# DAC_12bitController.net
KiCad netlist of a schematic drawn in EAGLE
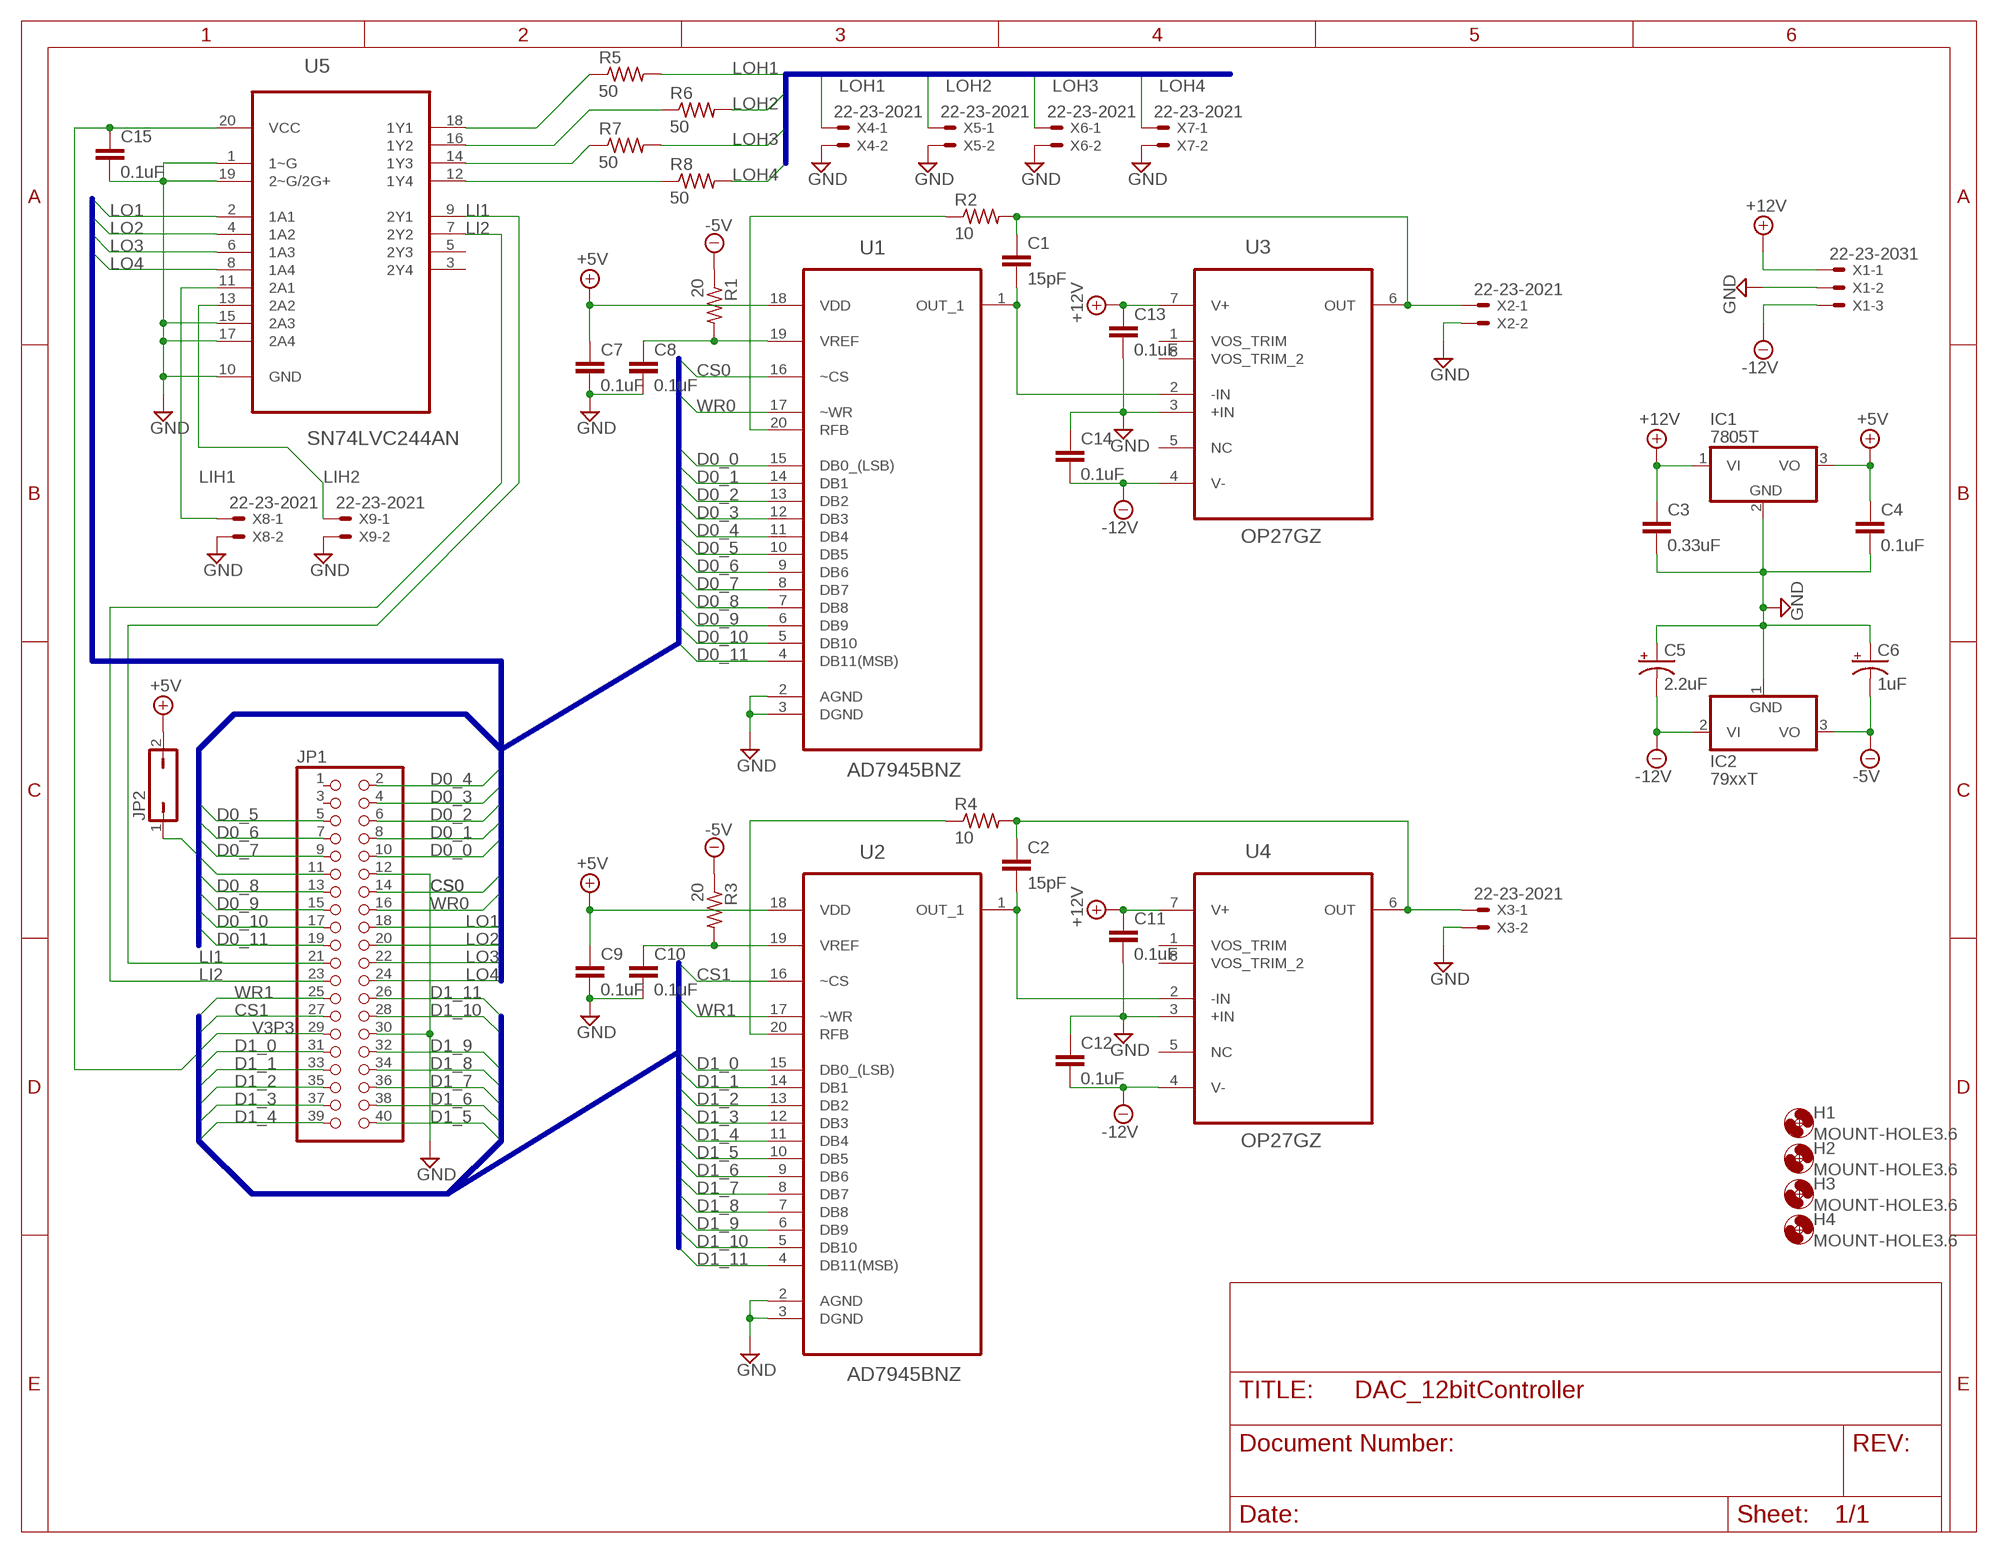
[diagram p0: schematic, sheet 1]

(export (version "E")
  (design (tool "Eeschema 10.0.6"))
  (components
    (comp (ref "C1")
      (value "15pF")
      (footprint "eagle-import:C5B2.5")
      (libsource (lib "eagle-import") (part "C5/2.5"))
    )
    (comp (ref "C2")
      (value "15pF")
      (footprint "eagle-import:C5B2.5")
      (libsource (lib "eagle-import") (part "C5/2.5"))
    )
    (comp (ref "C3")
      (value "0.33uF")
      (footprint "eagle-import:C5B2.5")
      (libsource (lib "eagle-import") (part "C5/2.5"))
    )
    (comp (ref "C4")
      (value "0.1uF")
      (footprint "eagle-import:C5B2.5")
      (libsource (lib "eagle-import") (part "C5/2.5"))
    )
    (comp (ref "C5")
      (value "2.2uF")
      (footprint "eagle-import:E2,5-7")
      (libsource (lib "eagle-import") (part "CPOL-USE2.5-7"))
    )
    (comp (ref "C6")
      (value "1uF")
      (footprint "eagle-import:E2,5-7")
      (libsource (lib "eagle-import") (part "CPOL-USE2.5-7"))
    )
    (comp (ref "C7")
      (value "0.1uF")
      (footprint "eagle-import:C5B2.5")
      (libsource (lib "eagle-import") (part "C5/2.5"))
    )
    (comp (ref "C8")
      (value "0.1uF")
      (footprint "eagle-import:C5B2.5")
      (libsource (lib "eagle-import") (part "C5/2.5"))
    )
    (comp (ref "C9")
      (value "0.1uF")
      (footprint "eagle-import:C5B2.5")
      (libsource (lib "eagle-import") (part "C5/2.5"))
    )
    (comp (ref "C10")
      (value "0.1uF")
      (footprint "eagle-import:C5B2.5")
      (libsource (lib "eagle-import") (part "C5/2.5"))
    )
    (comp (ref "C11")
      (value "0.1uF")
      (footprint "eagle-import:C5B2.5")
      (libsource (lib "eagle-import") (part "C5/2.5"))
    )
    (comp (ref "C12")
      (value "0.1uF")
      (footprint "eagle-import:C5B2.5")
      (libsource (lib "eagle-import") (part "C5/2.5"))
    )
    (comp (ref "C13")
      (value "0.1uF")
      (footprint "eagle-import:C5B2.5")
      (libsource (lib "eagle-import") (part "C5/2.5"))
    )
    (comp (ref "C14")
      (value "0.1uF")
      (footprint "eagle-import:C5B2.5")
      (libsource (lib "eagle-import") (part "C5/2.5"))
    )
    (comp (ref "C15")
      (value "0.1uF")
      (footprint "eagle-import:C5B2.5")
      (libsource (lib "eagle-import") (part "C5/2.5"))
    )
    (comp (ref "H1")
      (value "MOUNT-HOLE3.6")
      (footprint "eagle-import:3,6")
      (libsource (lib "eagle-import") (part "MOUNT-HOLE3.6"))
    )
    (comp (ref "H2")
      (value "MOUNT-HOLE3.6")
      (footprint "eagle-import:3,6")
      (libsource (lib "eagle-import") (part "MOUNT-HOLE3.6"))
    )
    (comp (ref "H3")
      (value "MOUNT-HOLE3.6")
      (footprint "eagle-import:3,6")
      (libsource (lib "eagle-import") (part "MOUNT-HOLE3.6"))
    )
    (comp (ref "H4")
      (value "MOUNT-HOLE3.6")
      (footprint "eagle-import:3,6")
      (libsource (lib "eagle-import") (part "MOUNT-HOLE3.6"))
    )
    (comp (ref "IC1")
      (value "7805T")
      (footprint "eagle-import:TO220H")
      (libsource (lib "eagle-import") (part "78T05"))
    )
    (comp (ref "IC2")
      (value "79xxT")
      (footprint "eagle-import:TO220H")
      (libsource (lib "eagle-import") (part "79T05"))
    )
    (comp (ref "JP1")
      (value "PINHD-2X20")
      (footprint "eagle-import:2X20")
      (libsource (lib "eagle-import") (part "PINHD-2X20"))
    )
    (comp (ref "JP2")
      (value "JP1Q")
      (footprint "eagle-import:JP1")
      (libsource (lib "eagle-import") (part "JP1Q"))
    )
    (comp (ref "R1")
      (value "20")
      (footprint "eagle-import:0207_10")
      (libsource (lib "eagle-import") (part "R-US_0207/10"))
    )
    (comp (ref "R2")
      (value "10")
      (footprint "eagle-import:0207_10")
      (libsource (lib "eagle-import") (part "R-US_0207/10"))
    )
    (comp (ref "R3")
      (value "20")
      (footprint "eagle-import:0207_10")
      (libsource (lib "eagle-import") (part "R-US_0207/10"))
    )
    (comp (ref "R4")
      (value "10")
      (footprint "eagle-import:0207_10")
      (libsource (lib "eagle-import") (part "R-US_0207/10"))
    )
    (comp (ref "R5")
      (value "50")
      (footprint "eagle-import:0207_10")
      (libsource (lib "eagle-import") (part "R-US_0207/10"))
    )
    (comp (ref "R6")
      (value "50")
      (footprint "eagle-import:0207_10")
      (libsource (lib "eagle-import") (part "R-US_0207/10"))
    )
    (comp (ref "R7")
      (value "50")
      (footprint "eagle-import:0207_10")
      (libsource (lib "eagle-import") (part "R-US_0207/10"))
    )
    (comp (ref "R8")
      (value "50")
      (footprint "eagle-import:0207_10")
      (libsource (lib "eagle-import") (part "R-US_0207/10"))
    )
    (comp (ref "U1")
      (value "AD7945BNZ")
      (footprint "eagle-import:DIP254P762X368-20")
      (fields (field (name "MPN") "AD7545AKNZ"))
      (libsource (lib "eagle-import") (part "AD7545AKNZ"))
    )
    (comp (ref "U2")
      (value "AD7945BNZ")
      (footprint "eagle-import:DIP254P762X368-20")
      (fields (field (name "MPN") "AD7545AKNZ"))
      (libsource (lib "eagle-import") (part "AD7545AKNZ"))
    )
    (comp (ref "U3")
      (value "OP27GZ")
      (footprint "eagle-import:DIP254P762X508-8")
      (libsource (lib "eagle-import") (part "OP27GZ"))
    )
    (comp (ref "U4")
      (value "OP27GZ")
      (footprint "eagle-import:DIP254P762X508-8")
      (libsource (lib "eagle-import") (part "OP27GZ"))
    )
    (comp (ref "U5")
      (value "SN74LVC244AN")
      (footprint "eagle-import:DIP254P762X508-20")
      (fields (field (name "MPN") "SN74LS244N"))
      (libsource (lib "eagle-import") (part "SN74LS244N"))
    )
    (comp (ref "X1")
      (value "22-23-2031")
      (footprint "eagle-import:22-23-2031")
      (fields (field (name "MF") "MOLEX"))
      (libsource (lib "eagle-import") (part "22-23-2031"))
    )
    (comp (ref "X2")
      (value "22-23-2021")
      (footprint "eagle-import:22-23-2021")
      (fields (field (name "MF") "MOLEX"))
      (libsource (lib "eagle-import") (part "22-23-2021"))
    )
    (comp (ref "X3")
      (value "22-23-2021")
      (footprint "eagle-import:22-23-2021")
      (fields (field (name "MF") "MOLEX"))
      (libsource (lib "eagle-import") (part "22-23-2021"))
    )
    (comp (ref "X4")
      (value "22-23-2021")
      (footprint "eagle-import:22-23-2021")
      (fields (field (name "MF") "MOLEX"))
      (libsource (lib "eagle-import") (part "22-23-2021"))
    )
    (comp (ref "X5")
      (value "22-23-2021")
      (footprint "eagle-import:22-23-2021")
      (fields (field (name "MF") "MOLEX"))
      (libsource (lib "eagle-import") (part "22-23-2021"))
    )
    (comp (ref "X6")
      (value "22-23-2021")
      (footprint "eagle-import:22-23-2021")
      (fields (field (name "MF") "MOLEX"))
      (libsource (lib "eagle-import") (part "22-23-2021"))
    )
    (comp (ref "X7")
      (value "22-23-2021")
      (footprint "eagle-import:22-23-2021")
      (fields (field (name "MF") "MOLEX"))
      (libsource (lib "eagle-import") (part "22-23-2021"))
    )
    (comp (ref "X8")
      (value "22-23-2021")
      (footprint "eagle-import:22-23-2021")
      (fields (field (name "MF") "MOLEX"))
      (libsource (lib "eagle-import") (part "22-23-2021"))
    )
    (comp (ref "X9")
      (value "22-23-2021")
      (footprint "eagle-import:22-23-2021")
      (fields (field (name "MF") "MOLEX"))
      (libsource (lib "eagle-import") (part "22-23-2021"))
    )
  )
  (nets
    (net (code "1") (name "+5V") (class "Default")
      (node (ref "C4") (pin "1") (pinfunction "1_1") (pintype "passive"))
      (node (ref "C7") (pin "1") (pinfunction "1_1") (pintype "passive"))
      (node (ref "C9") (pin "1") (pinfunction "1_1") (pintype "passive"))
      (node (ref "IC1") (pin "3") (pinfunction "VO_3") (pintype "passive"))
      (node (ref "JP2") (pin "2") (pinfunction "2_2") (pintype "passive"))
      (node (ref "U1") (pin "18") (pinfunction "VDD_18") (pintype "power_in"))
      (node (ref "U2") (pin "18") (pinfunction "VDD_18") (pintype "power_in"))
    )
    (net (code "2") (name "+12V") (class "Default")
      (node (ref "C11") (pin "1") (pinfunction "1_1") (pintype "passive"))
      (node (ref "C13") (pin "1") (pinfunction "1_1") (pintype "passive"))
      (node (ref "C3") (pin "1") (pinfunction "1_1") (pintype "passive"))
      (node (ref "IC1") (pin "1") (pinfunction "VI_1") (pintype "input"))
      (node (ref "U3") (pin "7") (pinfunction "V+_7") (pintype "power_in"))
      (node (ref "U4") (pin "7") (pinfunction "V+_7") (pintype "power_in"))
      (node (ref "X1") (pin "1") (pinfunction "S_1") (pintype "passive"))
    )
    (net (code "3") (name "-5V") (class "Default")
      (node (ref "C6") (pin "-") (pinfunction "-_-") (pintype "passive"))
      (node (ref "IC2") (pin "3") (pinfunction "VO_3") (pintype "passive"))
      (node (ref "R1") (pin "1") (pinfunction "1_1") (pintype "passive"))
      (node (ref "R3") (pin "1") (pinfunction "1_1") (pintype "passive"))
    )
    (net (code "4") (name "-12V") (class "Default")
      (node (ref "C12") (pin "2") (pinfunction "2_2") (pintype "passive"))
      (node (ref "C14") (pin "2") (pinfunction "2_2") (pintype "passive"))
      (node (ref "C5") (pin "-") (pinfunction "-_-") (pintype "passive"))
      (node (ref "IC2") (pin "2") (pinfunction "VI_2") (pintype "input"))
      (node (ref "U3") (pin "4") (pinfunction "V-_4") (pintype "power_in"))
      (node (ref "U4") (pin "4") (pinfunction "V-_4") (pintype "power_in"))
      (node (ref "X1") (pin "3") (pinfunction "S_3") (pintype "passive"))
    )
    (net (code "5") (name "/CS0") (class "Default")
      (node (ref "JP1") (pin "14") (pinfunction "14_14") (pintype "passive"))
      (node (ref "U1") (pin "16") (pinfunction "~{CS}_16") (pintype "input"))
    )
    (net (code "6") (name "/CS1") (class "Default")
      (node (ref "JP1") (pin "27") (pinfunction "27_27") (pintype "passive"))
      (node (ref "U2") (pin "16") (pinfunction "~{CS}_16") (pintype "input"))
    )
    (net (code "7") (name "/D0_0") (class "Default")
      (node (ref "JP1") (pin "10") (pinfunction "10_10") (pintype "passive"))
      (node (ref "U1") (pin "15") (pinfunction "DB0_(LSB)_15") (pintype "input"))
    )
    (net (code "8") (name "/D0_1") (class "Default")
      (node (ref "JP1") (pin "8") (pinfunction "8_8") (pintype "passive"))
      (node (ref "U1") (pin "14") (pinfunction "DB1_14") (pintype "input"))
    )
    (net (code "9") (name "/D0_2") (class "Default")
      (node (ref "JP1") (pin "6") (pinfunction "6_6") (pintype "passive"))
      (node (ref "U1") (pin "13") (pinfunction "DB2_13") (pintype "input"))
    )
    (net (code "10") (name "/D0_3") (class "Default")
      (node (ref "JP1") (pin "4") (pinfunction "4_4") (pintype "passive"))
      (node (ref "U1") (pin "12") (pinfunction "DB3_12") (pintype "input"))
    )
    (net (code "11") (name "/D0_4") (class "Default")
      (node (ref "JP1") (pin "2") (pinfunction "2_2") (pintype "passive"))
      (node (ref "U1") (pin "11") (pinfunction "DB4_11") (pintype "input"))
    )
    (net (code "12") (name "/D0_5") (class "Default")
      (node (ref "JP1") (pin "5") (pinfunction "5_5") (pintype "passive"))
      (node (ref "U1") (pin "10") (pinfunction "DB5_10") (pintype "input"))
    )
    (net (code "13") (name "/D0_6") (class "Default")
      (node (ref "JP1") (pin "7") (pinfunction "7_7") (pintype "passive"))
      (node (ref "U1") (pin "9") (pinfunction "DB6_9") (pintype "input"))
    )
    (net (code "14") (name "/D0_7") (class "Default")
      (node (ref "JP1") (pin "9") (pinfunction "9_9") (pintype "passive"))
      (node (ref "U1") (pin "8") (pinfunction "DB7_8") (pintype "input"))
    )
    (net (code "15") (name "/D0_8") (class "Default")
      (node (ref "JP1") (pin "13") (pinfunction "13_13") (pintype "passive"))
      (node (ref "U1") (pin "7") (pinfunction "DB8_7") (pintype "input"))
    )
    (net (code "16") (name "/D0_9") (class "Default")
      (node (ref "JP1") (pin "15") (pinfunction "15_15") (pintype "passive"))
      (node (ref "U1") (pin "6") (pinfunction "DB9_6") (pintype "input"))
    )
    (net (code "17") (name "/D0_10") (class "Default")
      (node (ref "JP1") (pin "17") (pinfunction "17_17") (pintype "passive"))
      (node (ref "U1") (pin "5") (pinfunction "DB10_5") (pintype "input"))
    )
    (net (code "18") (name "/D0_11") (class "Default")
      (node (ref "JP1") (pin "19") (pinfunction "19_19") (pintype "passive"))
      (node (ref "U1") (pin "4") (pinfunction "DB11(MSB)_4") (pintype "input"))
    )
    (net (code "19") (name "/D1_0") (class "Default")
      (node (ref "JP1") (pin "31") (pinfunction "31_31") (pintype "passive"))
      (node (ref "U2") (pin "15") (pinfunction "DB0_(LSB)_15") (pintype "input"))
    )
    (net (code "20") (name "/D1_1") (class "Default")
      (node (ref "JP1") (pin "33") (pinfunction "33_33") (pintype "passive"))
      (node (ref "U2") (pin "14") (pinfunction "DB1_14") (pintype "input"))
    )
    (net (code "21") (name "/D1_2") (class "Default")
      (node (ref "JP1") (pin "35") (pinfunction "35_35") (pintype "passive"))
      (node (ref "U2") (pin "13") (pinfunction "DB2_13") (pintype "input"))
    )
    (net (code "22") (name "/D1_3") (class "Default")
      (node (ref "JP1") (pin "37") (pinfunction "37_37") (pintype "passive"))
      (node (ref "U2") (pin "12") (pinfunction "DB3_12") (pintype "input"))
    )
    (net (code "23") (name "/D1_4") (class "Default")
      (node (ref "JP1") (pin "39") (pinfunction "39_39") (pintype "passive"))
      (node (ref "U2") (pin "11") (pinfunction "DB4_11") (pintype "input"))
    )
    (net (code "24") (name "/D1_5") (class "Default")
      (node (ref "JP1") (pin "40") (pinfunction "40_40") (pintype "passive"))
      (node (ref "U2") (pin "10") (pinfunction "DB5_10") (pintype "input"))
    )
    (net (code "25") (name "/D1_6") (class "Default")
      (node (ref "JP1") (pin "38") (pinfunction "38_38") (pintype "passive"))
      (node (ref "U2") (pin "9") (pinfunction "DB6_9") (pintype "input"))
    )
    (net (code "26") (name "/D1_7") (class "Default")
      (node (ref "JP1") (pin "36") (pinfunction "36_36") (pintype "passive"))
      (node (ref "U2") (pin "8") (pinfunction "DB7_8") (pintype "input"))
    )
    (net (code "27") (name "/D1_8") (class "Default")
      (node (ref "JP1") (pin "34") (pinfunction "34_34") (pintype "passive"))
      (node (ref "U2") (pin "7") (pinfunction "DB8_7") (pintype "input"))
    )
    (net (code "28") (name "/D1_9") (class "Default")
      (node (ref "JP1") (pin "32") (pinfunction "32_32") (pintype "passive"))
      (node (ref "U2") (pin "6") (pinfunction "DB9_6") (pintype "input"))
    )
    (net (code "29") (name "/D1_10") (class "Default")
      (node (ref "JP1") (pin "28") (pinfunction "28_28") (pintype "passive"))
      (node (ref "U2") (pin "5") (pinfunction "DB10_5") (pintype "input"))
    )
    (net (code "30") (name "/D1_11") (class "Default")
      (node (ref "JP1") (pin "26") (pinfunction "26_26") (pintype "passive"))
      (node (ref "U2") (pin "4") (pinfunction "DB11(MSB)_4") (pintype "input"))
    )
    (net (code "31") (name "/LI1") (class "Default")
      (node (ref "JP1") (pin "21") (pinfunction "21_21") (pintype "passive"))
      (node (ref "U5") (pin "9") (pinfunction "2Y1_9") (pintype "output"))
    )
    (net (code "32") (name "/LI2") (class "Default")
      (node (ref "JP1") (pin "23") (pinfunction "23_23") (pintype "passive"))
      (node (ref "U5") (pin "7") (pinfunction "2Y2_7") (pintype "output"))
    )
    (net (code "33") (name "/LIH1") (class "Default")
      (node (ref "U5") (pin "11") (pinfunction "2A1_11") (pintype "input"))
      (node (ref "X8") (pin "1") (pinfunction "S_1") (pintype "passive"))
    )
    (net (code "34") (name "/LIH2") (class "Default")
      (node (ref "U5") (pin "13") (pinfunction "2A2_13") (pintype "input"))
      (node (ref "X9") (pin "1") (pinfunction "S_1") (pintype "passive"))
    )
    (net (code "35") (name "/LO1") (class "Default")
      (node (ref "JP1") (pin "18") (pinfunction "18_18") (pintype "passive"))
      (node (ref "U5") (pin "2") (pinfunction "1A1_2") (pintype "input"))
    )
    (net (code "36") (name "/LO2") (class "Default")
      (node (ref "JP1") (pin "20") (pinfunction "20_20") (pintype "passive"))
      (node (ref "U5") (pin "4") (pinfunction "1A2_4") (pintype "input"))
    )
    (net (code "37") (name "/LO3") (class "Default")
      (node (ref "JP1") (pin "22") (pinfunction "22_22") (pintype "passive"))
      (node (ref "U5") (pin "6") (pinfunction "1A3_6") (pintype "input"))
    )
    (net (code "38") (name "/LO4") (class "Default")
      (node (ref "JP1") (pin "24") (pinfunction "24_24") (pintype "passive"))
      (node (ref "U5") (pin "8") (pinfunction "1A4_8") (pintype "input"))
    )
    (net (code "39") (name "/LOH1") (class "Default")
      (node (ref "R5") (pin "2") (pinfunction "2_2") (pintype "passive"))
      (node (ref "X4") (pin "1") (pinfunction "S_1") (pintype "passive"))
    )
    (net (code "40") (name "/LOH2") (class "Default")
      (node (ref "R6") (pin "2") (pinfunction "2_2") (pintype "passive"))
      (node (ref "X5") (pin "1") (pinfunction "S_1") (pintype "passive"))
    )
    (net (code "41") (name "/LOH3") (class "Default")
      (node (ref "R7") (pin "2") (pinfunction "2_2") (pintype "passive"))
      (node (ref "X6") (pin "1") (pinfunction "S_1") (pintype "passive"))
    )
    (net (code "42") (name "/LOH4") (class "Default")
      (node (ref "R8") (pin "2") (pinfunction "2_2") (pintype "passive"))
      (node (ref "X7") (pin "1") (pinfunction "S_1") (pintype "passive"))
    )
    (net (code "43") (name "/V3P3") (class "Default")
      (node (ref "C15") (pin "1") (pinfunction "1_1") (pintype "passive"))
      (node (ref "JP1") (pin "29") (pinfunction "29_29") (pintype "passive"))
      (node (ref "U5") (pin "20") (pinfunction "VCC_20") (pintype "power_in"))
    )
    (net (code "44") (name "/WR0") (class "Default")
      (node (ref "JP1") (pin "16") (pinfunction "16_16") (pintype "passive"))
      (node (ref "U1") (pin "17") (pinfunction "~{WR}_17") (pintype "input"))
    )
    (net (code "45") (name "/WR1") (class "Default")
      (node (ref "JP1") (pin "25") (pinfunction "25_25") (pintype "passive"))
      (node (ref "U2") (pin "17") (pinfunction "~{WR}_17") (pintype "input"))
    )
    (net (code "46") (name "GND") (class "Default")
      (node (ref "C10") (pin "2") (pinfunction "2_2") (pintype "passive"))
      (node (ref "C11") (pin "2") (pinfunction "2_2") (pintype "passive"))
      (node (ref "C12") (pin "1") (pinfunction "1_1") (pintype "passive"))
      (node (ref "C13") (pin "2") (pinfunction "2_2") (pintype "passive"))
      (node (ref "C14") (pin "1") (pinfunction "1_1") (pintype "passive"))
      (node (ref "C15") (pin "2") (pinfunction "2_2") (pintype "passive"))
      (node (ref "C3") (pin "2") (pinfunction "2_2") (pintype "passive"))
      (node (ref "C4") (pin "2") (pinfunction "2_2") (pintype "passive"))
      (node (ref "C5") (pin "+") (pinfunction "+_+") (pintype "passive"))
      (node (ref "C6") (pin "+") (pinfunction "+_+") (pintype "passive"))
      (node (ref "C7") (pin "2") (pinfunction "2_2") (pintype "passive"))
      (node (ref "C8") (pin "2") (pinfunction "2_2") (pintype "passive"))
      (node (ref "C9") (pin "2") (pinfunction "2_2") (pintype "passive"))
      (node (ref "IC1") (pin "2") (pinfunction "GND_2") (pintype "passive"))
      (node (ref "IC2") (pin "1") (pinfunction "GND_1") (pintype "passive"))
      (node (ref "JP1") (pin "12") (pinfunction "12_12") (pintype "passive"))
      (node (ref "JP1") (pin "30") (pinfunction "30_30") (pintype "passive"))
      (node (ref "U1") (pin "2") (pinfunction "AGND_2") (pintype "passive"))
      (node (ref "U1") (pin "3") (pinfunction "DGND_3") (pintype "passive"))
      (node (ref "U2") (pin "2") (pinfunction "AGND_2") (pintype "passive"))
      (node (ref "U2") (pin "3") (pinfunction "DGND_3") (pintype "passive"))
      (node (ref "U3") (pin "3") (pinfunction "+IN_3") (pintype "input"))
      (node (ref "U4") (pin "3") (pinfunction "+IN_3") (pintype "input"))
      (node (ref "U5") (pin "1") (pinfunction "1~{G}_1") (pintype "input"))
      (node (ref "U5") (pin "10") (pinfunction "GND_10") (pintype "passive"))
      (node (ref "U5") (pin "15") (pinfunction "2A3_15") (pintype "input"))
      (node (ref "U5") (pin "17") (pinfunction "2A4_17") (pintype "input"))
      (node (ref "U5") (pin "19") (pinfunction "2~{G/2G+}_19") (pintype "input"))
      (node (ref "X1") (pin "2") (pinfunction "S_2") (pintype "passive"))
      (node (ref "X2") (pin "2") (pinfunction "S_2") (pintype "passive"))
      (node (ref "X3") (pin "2") (pinfunction "S_2") (pintype "passive"))
      (node (ref "X4") (pin "2") (pinfunction "S_2") (pintype "passive"))
      (node (ref "X5") (pin "2") (pinfunction "S_2") (pintype "passive"))
      (node (ref "X6") (pin "2") (pinfunction "S_2") (pintype "passive"))
      (node (ref "X7") (pin "2") (pinfunction "S_2") (pintype "passive"))
      (node (ref "X8") (pin "2") (pinfunction "S_2") (pintype "passive"))
      (node (ref "X9") (pin "2") (pinfunction "S_2") (pintype "passive"))
    )
    (net (code "47") (name "Net-(JP1-Pad11)") (class "Default")
      (node (ref "JP1") (pin "11") (pinfunction "11_11") (pintype "passive"))
      (node (ref "JP2") (pin "1") (pinfunction "1_1") (pintype "passive"))
    )
    (net (code "48") (name "Net-(U1-OUT_1)") (class "Default")
      (node (ref "C1") (pin "2") (pinfunction "2_2") (pintype "passive"))
      (node (ref "U1") (pin "1") (pinfunction "OUT_1_1") (pintype "output"))
      (node (ref "U3") (pin "2") (pinfunction "-IN_2") (pintype "input"))
    )
    (net (code "49") (name "Net-(U1-RFB)") (class "Default")
      (node (ref "R2") (pin "1") (pinfunction "1_1") (pintype "passive"))
      (node (ref "U1") (pin "20") (pinfunction "RFB_20") (pintype "input"))
    )
    (net (code "50") (name "Net-(U1-VREF)") (class "Default")
      (node (ref "C8") (pin "1") (pinfunction "1_1") (pintype "passive"))
      (node (ref "R1") (pin "2") (pinfunction "2_2") (pintype "passive"))
      (node (ref "U1") (pin "19") (pinfunction "VREF_19") (pintype "input"))
    )
    (net (code "51") (name "Net-(U2-OUT_1)") (class "Default")
      (node (ref "C2") (pin "2") (pinfunction "2_2") (pintype "passive"))
      (node (ref "U2") (pin "1") (pinfunction "OUT_1_1") (pintype "output"))
      (node (ref "U4") (pin "2") (pinfunction "-IN_2") (pintype "input"))
    )
    (net (code "52") (name "Net-(U2-RFB)") (class "Default")
      (node (ref "R4") (pin "1") (pinfunction "1_1") (pintype "passive"))
      (node (ref "U2") (pin "20") (pinfunction "RFB_20") (pintype "input"))
    )
    (net (code "53") (name "Net-(U2-VREF)") (class "Default")
      (node (ref "C10") (pin "1") (pinfunction "1_1") (pintype "passive"))
      (node (ref "R3") (pin "2") (pinfunction "2_2") (pintype "passive"))
      (node (ref "U2") (pin "19") (pinfunction "VREF_19") (pintype "input"))
    )
    (net (code "54") (name "Net-(U3-OUT)") (class "Default")
      (node (ref "C1") (pin "1") (pinfunction "1_1") (pintype "passive"))
      (node (ref "R2") (pin "2") (pinfunction "2_2") (pintype "passive"))
      (node (ref "U3") (pin "6") (pinfunction "OUT_6") (pintype "output"))
      (node (ref "X2") (pin "1") (pinfunction "S_1") (pintype "passive"))
    )
    (net (code "55") (name "Net-(U4-OUT)") (class "Default")
      (node (ref "C2") (pin "1") (pinfunction "1_1") (pintype "passive"))
      (node (ref "R4") (pin "2") (pinfunction "2_2") (pintype "passive"))
      (node (ref "U4") (pin "6") (pinfunction "OUT_6") (pintype "output"))
      (node (ref "X3") (pin "1") (pinfunction "S_1") (pintype "passive"))
    )
    (net (code "56") (name "Net-(U5-1Y1)") (class "Default")
      (node (ref "R5") (pin "1") (pinfunction "1_1") (pintype "passive"))
      (node (ref "U5") (pin "18") (pinfunction "1Y1_18") (pintype "output"))
    )
    (net (code "57") (name "Net-(U5-1Y2)") (class "Default")
      (node (ref "R6") (pin "1") (pinfunction "1_1") (pintype "passive"))
      (node (ref "U5") (pin "16") (pinfunction "1Y2_16") (pintype "output"))
    )
    (net (code "58") (name "Net-(U5-1Y3)") (class "Default")
      (node (ref "R7") (pin "1") (pinfunction "1_1") (pintype "passive"))
      (node (ref "U5") (pin "14") (pinfunction "1Y3_14") (pintype "output"))
    )
    (net (code "59") (name "Net-(U5-1Y4)") (class "Default")
      (node (ref "R8") (pin "1") (pinfunction "1_1") (pintype "passive"))
      (node (ref "U5") (pin "12") (pinfunction "1Y4_12") (pintype "output"))
    )
    (net (code "60") (name "unconnected-(JP1-Pad1)") (class "Default")
      (node (ref "JP1") (pin "1") (pinfunction "1_1") (pintype "passive"))
    )
    (net (code "61") (name "unconnected-(JP1-Pad3)") (class "Default")
      (node (ref "JP1") (pin "3") (pinfunction "3_3") (pintype "passive"))
    )
    (net (code "62") (name "unconnected-(U3-NC-Pad5)") (class "Default")
      (node (ref "U3") (pin "5") (pinfunction "NC_5") (pintype "no_connect"))
    )
    (net (code "63") (name "unconnected-(U3-VOS_TRIM-Pad1)") (class "Default")
      (node (ref "U3") (pin "1") (pinfunction "VOS_TRIM_1") (pintype "passive"))
    )
    (net (code "64") (name "unconnected-(U3-VOS_TRIM_2-Pad8)") (class "Default")
      (node (ref "U3") (pin "8") (pinfunction "VOS_TRIM_2_8") (pintype "passive"))
    )
    (net (code "65") (name "unconnected-(U4-NC-Pad5)") (class "Default")
      (node (ref "U4") (pin "5") (pinfunction "NC_5") (pintype "no_connect"))
    )
    (net (code "66") (name "unconnected-(U4-VOS_TRIM-Pad1)") (class "Default")
      (node (ref "U4") (pin "1") (pinfunction "VOS_TRIM_1") (pintype "passive"))
    )
    (net (code "67") (name "unconnected-(U4-VOS_TRIM_2-Pad8)") (class "Default")
      (node (ref "U4") (pin "8") (pinfunction "VOS_TRIM_2_8") (pintype "passive"))
    )
    (net (code "68") (name "unconnected-(U5-2Y3-Pad5)") (class "Default")
      (node (ref "U5") (pin "5") (pinfunction "2Y3_5") (pintype "output"))
    )
    (net (code "69") (name "unconnected-(U5-2Y4-Pad3)") (class "Default")
      (node (ref "U5") (pin "3") (pinfunction "2Y4_3") (pintype "output"))
    )
  )
)
